# Sheet1.net
KiCad netlist of a schematic drawn in Altium Designer
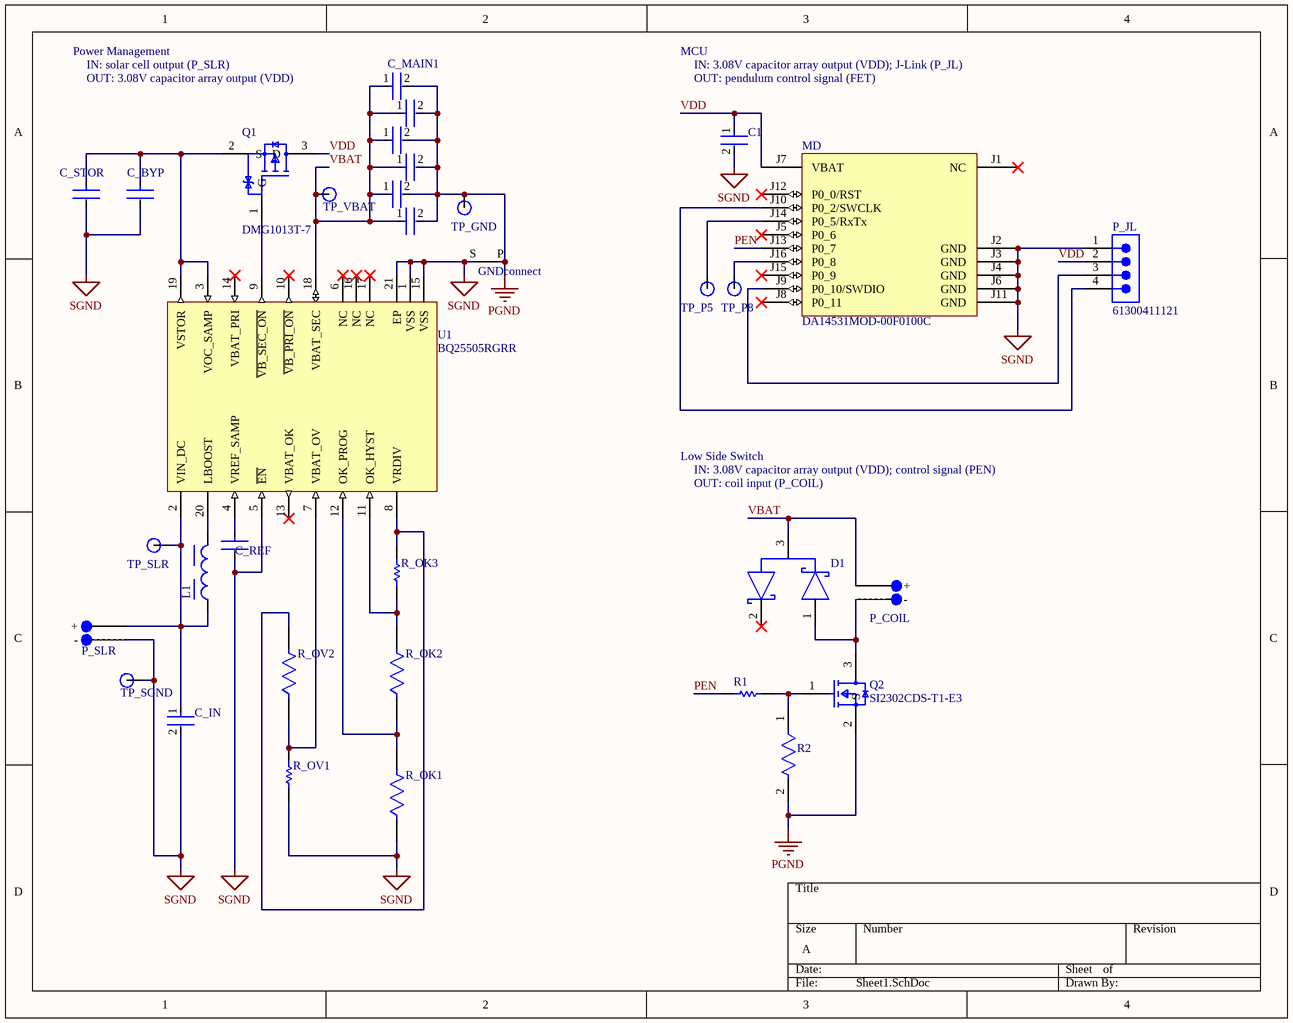
[diagram p0: Sheet1.SchDoc]

(export (version "E")
  (design (tool "Eeschema 10.0.6"))
  (components
    (comp (ref "C1")
      (value "GRM188R72A104KA35D")
      (footprint "FP-GRM188-0_1-e0_2_0_5-IPC_B")
      (description "Chip Multilayer Ceramic Capacitors for General Purpose, 0603, 0.10uF, X7R, 15%, 10%, 100V")
      (fields (field (name "VOLTAGE") "100V") (field (name "TOLERANCE") "10%"))
      (libsource (lib "Altium Content Vault") (part "11868f565c42a9108669ba33697ecf6"))
    )
    (comp (ref "C_BYP")
      (value "CGA4J1X7R1H475K125AC")
      (footprint "FP-CGA4J-IPC_C")
      (description "Cap Ceramic 4.7uF 50V X7R 10% Pad SMD 0805 +125°C Automotive T/R")
      (libsource (lib "") (part "b4654b650e69147ec39a6b967a45e02_1"))
    )
    (comp (ref "C_IN")
      (value "CGA4J1X7R1H475K125AC")
      (footprint "FP-CGA4J-IPC_C")
      (description "Cap Ceramic 4.7uF 50V X7R 10% Pad SMD 0805 +125°C Automotive T/R")
      (libsource (lib "Altium Content Vault") (part "b4654b650e69147ec39a6b967a45e02"))
    )
    (comp (ref "C_MAIN1")
      (value "GRM32ER60J227ME05L")
      (footprint "FP-GRM32E-0_3-MFG")
      (description "Chip Multilayer Ceramic Capacitors for General Purpose, 1210, 220uF, X5R, 15%, 20%, 6.3V")
      (fields (field (name "TOLERANCE") "20%"))
      (libsource (lib "Altium Content Vault") (part "b4654b650e69147ec39a6b967a45e02"))
    )
    (comp (ref "C_MAIN2")
      (value "GRM32ER60J227ME05L")
      (footprint "FP-GRM32E-0_3-MFG")
      (description "Chip Multilayer Ceramic Capacitors for General Purpose, 1210, 220uF, X5R, 15%, 20%, 6.3V")
      (fields (field (name "TOLERANCE") "20%"))
      (libsource (lib "Altium Content Vault") (part "b4654b650e69147ec39a6b967a45e02"))
    )
    (comp (ref "C_MAIN3")
      (value "GRM32ER60J227ME05L")
      (footprint "FP-GRM32E-0_3-MFG")
      (description "Chip Multilayer Ceramic Capacitors for General Purpose, 1210, 220uF, X5R, 15%, 20%, 6.3V")
      (fields (field (name "TOLERANCE") "20%"))
      (libsource (lib "Altium Content Vault") (part "b4654b650e69147ec39a6b967a45e02"))
    )
    (comp (ref "C_MAIN4")
      (value "GRM32ER60J227ME05L")
      (footprint "FP-GRM32E-0_3-MFG")
      (description "Chip Multilayer Ceramic Capacitors for General Purpose, 1210, 220uF, X5R, 15%, 20%, 6.3V")
      (fields (field (name "TOLERANCE") "20%"))
      (libsource (lib "Altium Content Vault") (part "b4654b650e69147ec39a6b967a45e02"))
    )
    (comp (ref "C_MAIN5")
      (value "GRM32ER60J227ME05L")
      (footprint "FP-GRM32E-0_3-MFG")
      (description "Chip Multilayer Ceramic Capacitors for General Purpose, 1210, 220uF, X5R, 15%, 20%, 6.3V")
      (fields (field (name "TOLERANCE") "20%"))
      (libsource (lib "Altium Content Vault") (part "b4654b650e69147ec39a6b967a45e02"))
    )
    (comp (ref "C_MAIN6")
      (value "GRM32ER60J227ME05L")
      (footprint "FP-GRM32E-0_3-MFG")
      (description "Chip Multilayer Ceramic Capacitors for General Purpose, 1210, 220uF, X5R, 15%, 20%, 6.3V")
      (fields (field (name "TOLERANCE") "20%"))
      (libsource (lib "Altium Content Vault") (part "b4654b650e69147ec39a6b967a45e02"))
    )
    (comp (ref "C_REF")
      (value "GCM188R72A103KA37D")
      (footprint "FP-GCM188-0_1-MFG")
      (description "Ceramic Capacitor for Automotive 10nF  ±10% 100VDC X7R 0603 Paper T/R")
      (fields (field (name "VOLTAGE") "100V") (field (name "TOLERANCE") "10%"))
      (libsource (lib "Altium Content Vault") (part "02cd4be3c70576c341d710602a673aa"))
    )
    (comp (ref "C_STOR")
      (value "GCM188R72A103KA37D")
      (footprint "FP-GCM188-0_1-MFG")
      (description "Ceramic Capacitor for Automotive 10nF  ±10% 100VDC X7R 0603 Paper T/R")
      (fields (field (name "VOLTAGE") "100V") (field (name "TOLERANCE") "10%"))
      (libsource (lib "Altium Content Vault") (part "02cd4be3c70576c341d710602a673aa"))
    )
    (comp (ref "D1")
      (value "BAT54STA")
      (footprint "FP-SOT523-MFG")
      (description "DIODE ARRAY SCHOTTKY 30V SOT23-3")
      (fields
        (field (name "OCTOPART") "https://octopart.com/bat54sta-diodes+inc.-326178")
        (field (name "MANUFACTURER") "Diodes Inc.")
      )
      (libsource (lib "Altium Content Vault") (part "3154784a5abab095c2c910d688c1447"))
    )
    (comp (ref "GNDconnect")
      (value "GNDconnect")
      (footprint "GNDconnect")
      (libsource (lib "Schlib1") (part "GNDconnect"))
    )
    (comp (ref "L1")
      (value "744031220")
      (footprint "WE-TPC_3816")
      (description "Tiny Power Inductor, SMT, Fixed, 22UH, .51A, .041 Ohm, 3816, We-tpc Series")
      (fields (field (name "TOLERANCE") "30%"))
      (libsource (lib "Altium Content Vault") (part "Inductor - 3"))
    )
    (comp (ref "MD")
      (value "DA14531MOD-00F0100C")
      (footprint "MN0016AA_MFG")
      (description "SmartBond TINY Bluetooth Low Energy Module")
      (libsource (lib "Altium Content Vault") (part "3c23fbc519b76c76d1d6908b3b5f111"))
    )
    (comp (ref "P_COIL")
      (value "Paired_pads")
      (footprint "Paired_pads")
      (libsource (lib "") (part "Paired_pads_1"))
    )
    (comp (ref "P_JL")
      (value "61300411121")
      (footprint "61300411121")
      (description "THT Vertical Pin Header WR-PHD, Pitch 2.54 mm, Single Row, 4 pins")
      (libsource (lib "Altium Content Vault") (part "Header_Male_1R_04P"))
    )
    (comp (ref "P_SLR")
      (value "Paired_pads")
      (footprint "Paired_pads")
      (libsource (lib "Schlib2") (part "Paired_pads"))
    )
    (comp (ref "Q1")
      (value "DMG1013T-7")
      (footprint "FP-SOT523-IPC_B")
      (description "MOSFET P-CH 20V 0.46A SOT-523")
      (libsource (lib "Altium Content Vault") (part "d2c0d31e441d0c4ace7f3b05f74b3be"))
    )
    (comp (ref "Q2")
      (value "SI2302CDS-T1-E3")
      (footprint "FP-S-03946-MFG")
      (description "MOSFET N-CH 20V 2.6A SOT-23")
      (fields
        (field (name "MANUFACTURER") "Vishay")
        (field (name "OCTOPART") "https://octopart.com/si2302cds-t1-e3-vishay-44452855")
      )
      (libsource (lib "Altium Content Vault") (part "3b9c635fedb024a5347a57b145af9cc"))
    )
    (comp (ref "R1")
      (value "ERJ-3EKF4700V")
      (footprint "RESC1608X55X30ML15T15")
      (description "Chip Resistor, 470 Ohm, +/- 1%, 0.1 W, -55 to 155 degC, 0603 (1608 Metric), RoHS, Tape and Reel")
      (fields (field (name "MANUFACTURER") "Panasonic"))
      (libsource (lib "Altium Content Vault") (part "RES-2"))
    )
    (comp (ref "R2")
      (value "RC0603FR-07100KL")
      (footprint "FP-RC0603-0_55-MFG")
      (description "RES SMD 100K OHM 1% 1/10W 0603")
      (fields (field (name "TOLERANCE") "1%"))
      (libsource (lib "") (part "1029c3af85768c4190bb7ad29bc67b5_1"))
    )
    (comp (ref "R_OK1")
      (value "CRCW06035M62FKEA")
      (footprint "FP-CRCW0603-e3-IPC_B")
      (description "RES Thick Film, 5.62MΩ, 1%, 0.1W, 100ppm/°C, 0603")
      (fields (field (name "TOLERANCE") "1%"))
      (libsource (lib "Altium Content Vault") (part "1029c3af85768c4190bb7ad29bc67b5"))
    )
    (comp (ref "R_OK2")
      (value "CRCW06035M49FKEA")
      (footprint "FP-CRCW0603-e3-IPC_C")
      (description "RES Thick Film, 5.49MΩ, 1%, 0.1W, 100ppm/°C, 0603")
      (fields (field (name "TOLERANCE") "1%"))
      (libsource (lib "Altium Content Vault") (part "1029c3af85768c4190bb7ad29bc67b5"))
    )
    (comp (ref "R_OK3")
      (value "CRCW06031M87FKEA")
      (footprint "RESC1609X50X30ML10T20")
      (fields (field (name "MANUFACTURER") "Vishay Dale"))
      (libsource (lib "Altium Content Vault") (part "RES"))
    )
    (comp (ref "R_OV1")
      (value "CRCW06037M68FKEA")
      (footprint "RESC0603(1608)_L")
      (description "7M68 0.1W 1% 0603 (1608 Metric)  SMD")
      (fields (field (name "POWER") "0.1 W") (field (name "TOLERANCE") "1 %"))
      (libsource (lib "Altium Content Vault") (part "RES"))
    )
    (comp (ref "R_OV2")
      (value "CRCW06035M36FKEA")
      (footprint "FP-CRCW0603-e3-IPC_C")
      (description "RES Thick Film, 5.36MΩ, 1%, 0.1W, 100ppm/°C, 0603")
      (fields (field (name "TOLERANCE") "1%"))
      (libsource (lib "Altium Content Vault") (part "1029c3af85768c4190bb7ad29bc67b5"))
    )
    (comp (ref "TP_GND") (value "TP") (footprint "Test_point") (libsource (lib "Schlib3") (part "TP")))
    (comp (ref "TP_P5") (value "TP") (footprint "Test_point") (libsource (lib "Schlib3") (part "TP")))
    (comp (ref "TP_P8") (value "TP") (footprint "Test_point") (libsource (lib "Schlib3") (part "TP")))
    (comp (ref "TP_SGND") (value "TP") (footprint "Test_point") (libsource (lib "Schlib3") (part "TP")))
    (comp (ref "TP_SLR") (value "TP") (footprint "Test_point") (libsource (lib "Schlib3") (part "TP")))
    (comp (ref "TP_VBAT") (value "TP") (footprint "Test_point") (libsource (lib "Schlib3") (part "TP")))
    (comp (ref "U1")
      (value "BQ25505RGRR")
      (footprint "RGR0020A_V")
      (fields (field (name "GENERIC PART NUMBER") "BQ25505"))
      (libsource (lib "Altium Content Vault") (part "TI-BQ25505-RGR-20"))
    )
  )
  (nets
    (net (code "1") (name "/PEN") (class "Default")
      (node (ref "MD") (pin "J13") (pinfunction "P0_7_J13") (pintype "bidirectional"))
      (node (ref "R1") (pin "1") (pinfunction "1_1") (pintype "passive"))
    )
    (net (code "2") (name "/VBAT") (class "Default")
      (node (ref "C_MAIN1") (pin "1") (pinfunction "1_1") (pintype "passive"))
      (node (ref "C_MAIN2") (pin "1") (pinfunction "1_1") (pintype "passive"))
      (node (ref "C_MAIN3") (pin "1") (pinfunction "1_1") (pintype "passive"))
      (node (ref "C_MAIN4") (pin "1") (pinfunction "1_1") (pintype "passive"))
      (node (ref "C_MAIN5") (pin "1") (pinfunction "1_1") (pintype "passive"))
      (node (ref "C_MAIN6") (pin "1") (pinfunction "1_1") (pintype "passive"))
      (node (ref "D1") (pin "3") (pinfunction "3_3") (pintype "passive"))
      (node (ref "P_COIL") (pin "1") (pinfunction "+_1") (pintype "passive"))
      (node (ref "TP_VBAT") (pin "1") (pinfunction "TP_1") (pintype "passive"))
      (node (ref "U1") (pin "18") (pinfunction "VBAT_SEC_18") (pintype "bidirectional"))
    )
    (net (code "3") (name "/VDD") (class "Default")
      (node (ref "C1") (pin "1") (pinfunction "1_1") (pintype "passive"))
      (node (ref "MD") (pin "J7") (pinfunction "VBAT_J7") (pintype "power_in"))
      (node (ref "P_JL") (pin "2") (pinfunction "2_2") (pintype "passive"))
      (node (ref "Q1") (pin "3") (pinfunction "D_3") (pintype "passive"))
    )
    (net (code "4") (name "Net-(MD-P0_2{slash}SWCLK)") (class "Default")
      (node (ref "MD") (pin "J10") (pinfunction "P0_2/SWCLK_J10") (pintype "bidirectional"))
      (node (ref "P_JL") (pin "4") (pinfunction "4_4") (pintype "passive"))
    )
    (net (code "5") (name "Net-(MD-P0_5{slash}RxTx)") (class "Default")
      (node (ref "MD") (pin "J14") (pinfunction "P0_5/RxTx_J14") (pintype "bidirectional"))
      (node (ref "TP_P5") (pin "1") (pinfunction "TP_1") (pintype "passive"))
    )
    (net (code "6") (name "Net-(MD-P0_8)") (class "Default")
      (node (ref "MD") (pin "J16") (pinfunction "P0_8_J16") (pintype "bidirectional"))
      (node (ref "TP_P8") (pin "1") (pinfunction "TP_1") (pintype "passive"))
    )
    (net (code "7") (name "Net-(MD-P0_10{slash}SWDIO)") (class "Default")
      (node (ref "MD") (pin "J9") (pinfunction "P0_10/SWDIO_J9") (pintype "bidirectional"))
      (node (ref "P_JL") (pin "3") (pinfunction "3_3") (pintype "passive"))
    )
    (net (code "8") (name "Net-(P_COIL--)") (class "Default")
      (node (ref "D1") (pin "1") (pinfunction "1_1") (pintype "passive"))
      (node (ref "P_COIL") (pin "2") (pinfunction "-_2") (pintype "passive"))
      (node (ref "Q2") (pin "3") (pinfunction "D_3") (pintype "passive"))
    )
    (net (code "9") (name "Net-(P_SLR-+)") (class "Default")
      (node (ref "C_IN") (pin "1") (pinfunction "1_1") (pintype "passive"))
      (node (ref "L1") (pin "1") (pinfunction "1_1") (pintype "passive"))
      (node (ref "P_SLR") (pin "1") (pinfunction "+_1") (pintype "passive"))
      (node (ref "TP_SLR") (pin "1") (pinfunction "TP_1") (pintype "passive"))
      (node (ref "U1") (pin "2") (pinfunction "VIN_DC_2") (pintype "power_in"))
    )
    (net (code "10") (name "Net-(Q1-G)") (class "Default")
      (node (ref "Q1") (pin "1") (pinfunction "G_1") (pintype "passive"))
      (node (ref "U1") (pin "9") (pinfunction "~{VB_SEC_ON}_9") (pintype "output"))
    )
    (net (code "11") (name "Net-(Q1-S)") (class "Default")
      (node (ref "C_BYP") (pin "1") (pinfunction "1_1") (pintype "passive"))
      (node (ref "C_STOR") (pin "1") (pinfunction "1_1") (pintype "passive"))
      (node (ref "Q1") (pin "2") (pinfunction "S_2") (pintype "passive"))
      (node (ref "U1") (pin "19") (pinfunction "VSTOR_19") (pintype "output"))
      (node (ref "U1") (pin "3") (pinfunction "VOC_SAMP_3") (pintype "input"))
    )
    (net (code "12") (name "Net-(Q2-G)") (class "Default")
      (node (ref "Q2") (pin "1") (pinfunction "G_1") (pintype "passive"))
      (node (ref "R1") (pin "2") (pinfunction "2_2") (pintype "passive"))
      (node (ref "R2") (pin "1") (pinfunction "1_1") (pintype "passive"))
    )
    (net (code "13") (name "Net-(U1-LBOOST)") (class "Default")
      (node (ref "L1") (pin "2") (pinfunction "2_2") (pintype "passive"))
      (node (ref "U1") (pin "20") (pinfunction "LBOOST_20") (pintype "power_in"))
    )
    (net (code "14") (name "Net-(U1-OK_HYST)") (class "Default")
      (node (ref "R_OK2") (pin "2") (pinfunction "2_2") (pintype "passive"))
      (node (ref "R_OK3") (pin "1") (pinfunction "1_1") (pintype "passive"))
      (node (ref "U1") (pin "11") (pinfunction "OK_HYST_11") (pintype "input"))
    )
    (net (code "15") (name "Net-(U1-OK_PROG)") (class "Default")
      (node (ref "R_OK1") (pin "2") (pinfunction "2_2") (pintype "passive"))
      (node (ref "R_OK2") (pin "1") (pinfunction "1_1") (pintype "passive"))
      (node (ref "U1") (pin "12") (pinfunction "OK_PROG_12") (pintype "input"))
    )
    (net (code "16") (name "Net-(U1-VBAT_OV)") (class "Default")
      (node (ref "R_OV1") (pin "2") (pinfunction "2_2") (pintype "passive"))
      (node (ref "R_OV2") (pin "1") (pinfunction "1_1") (pintype "passive"))
      (node (ref "U1") (pin "7") (pinfunction "VBAT_OV_7") (pintype "input"))
    )
    (net (code "17") (name "Net-(U1-VRDIV)") (class "Default")
      (node (ref "R_OK3") (pin "2") (pinfunction "2_2") (pintype "passive"))
      (node (ref "R_OV2") (pin "2") (pinfunction "2_2") (pintype "passive"))
      (node (ref "U1") (pin "8") (pinfunction "VRDIV_8") (pintype "power_in"))
    )
    (net (code "18") (name "Net-(U1-VREF_SAMP)") (class "Default")
      (node (ref "C_REF") (pin "1") (pinfunction "1_1") (pintype "passive"))
      (node (ref "U1") (pin "4") (pinfunction "VREF_SAMP_4") (pintype "input"))
    )
    (net (code "19") (name "PGND") (class "Default")
      (node (ref "C_MAIN1") (pin "2") (pinfunction "2_2") (pintype "passive"))
      (node (ref "C_MAIN2") (pin "2") (pinfunction "2_2") (pintype "passive"))
      (node (ref "C_MAIN3") (pin "2") (pinfunction "2_2") (pintype "passive"))
      (node (ref "C_MAIN4") (pin "2") (pinfunction "2_2") (pintype "passive"))
      (node (ref "C_MAIN5") (pin "2") (pinfunction "2_2") (pintype "passive"))
      (node (ref "C_MAIN6") (pin "2") (pinfunction "2_2") (pintype "passive"))
      (node (ref "GNDconnect") (pin "P") (pinfunction "P_P") (pintype "passive"))
      (node (ref "Q2") (pin "2") (pinfunction "S_2") (pintype "passive"))
      (node (ref "R2") (pin "2") (pinfunction "2_2") (pintype "passive"))
      (node (ref "TP_GND") (pin "1") (pinfunction "TP_1") (pintype "passive"))
    )
    (net (code "20") (name "SGND") (class "Default")
      (node (ref "C1") (pin "2") (pinfunction "2_2") (pintype "passive"))
      (node (ref "C_BYP") (pin "2") (pinfunction "2_2") (pintype "passive"))
      (node (ref "C_IN") (pin "2") (pinfunction "2_2") (pintype "passive"))
      (node (ref "C_REF") (pin "2") (pinfunction "2_2") (pintype "passive"))
      (node (ref "C_STOR") (pin "2") (pinfunction "2_2") (pintype "passive"))
      (node (ref "GNDconnect") (pin "S") (pinfunction "S_S") (pintype "passive"))
      (node (ref "MD") (pin "J11") (pinfunction "GND_J11") (pintype "power_in"))
      (node (ref "MD") (pin "J2") (pinfunction "GND_J2") (pintype "power_in"))
      (node (ref "MD") (pin "J3") (pinfunction "GND_J3") (pintype "power_in"))
      (node (ref "MD") (pin "J4") (pinfunction "GND_J4") (pintype "power_in"))
      (node (ref "MD") (pin "J6") (pinfunction "GND_J6") (pintype "power_in"))
      (node (ref "P_JL") (pin "1") (pinfunction "1_1") (pintype "passive"))
      (node (ref "P_SLR") (pin "2") (pinfunction "-_2") (pintype "passive"))
      (node (ref "R_OK1") (pin "1") (pinfunction "1_1") (pintype "passive"))
      (node (ref "R_OV1") (pin "1") (pinfunction "1_1") (pintype "passive"))
      (node (ref "TP_SGND") (pin "1") (pinfunction "TP_1") (pintype "passive"))
      (node (ref "U1") (pin "1") (pinfunction "VSS_1") (pintype "power_in"))
      (node (ref "U1") (pin "15") (pinfunction "VSS_15") (pintype "power_in"))
      (node (ref "U1") (pin "21") (pinfunction "EP_21") (pintype "passive"))
      (node (ref "U1") (pin "5") (pinfunction "~{EN}_5") (pintype "input"))
    )
    (net (code "21") (name "unconnected-(D1-Pad2)") (class "Default")
      (node (ref "D1") (pin "2") (pinfunction "2_2") (pintype "passive+no_connect"))
    )
    (net (code "22") (name "unconnected-(MD-NC-PadJ1)") (class "Default")
      (node (ref "MD") (pin "J1") (pinfunction "NC_J1") (pintype "passive+no_connect"))
    )
    (net (code "23") (name "unconnected-(MD-P0_0{slash}RST-PadJ12)") (class "Default")
      (node (ref "MD") (pin "J12") (pinfunction "P0_0/RST_J12") (pintype "bidirectional+no_connect"))
    )
    (net (code "24") (name "unconnected-(MD-P0_6-PadJ5)") (class "Default")
      (node (ref "MD") (pin "J5") (pinfunction "P0_6_J5") (pintype "bidirectional+no_connect"))
    )
    (net (code "25") (name "unconnected-(MD-P0_9-PadJ15)") (class "Default")
      (node (ref "MD") (pin "J15") (pinfunction "P0_9_J15") (pintype "bidirectional+no_connect"))
    )
    (net (code "26") (name "unconnected-(MD-P0_11-PadJ8)") (class "Default")
      (node (ref "MD") (pin "J8") (pinfunction "P0_11_J8") (pintype "bidirectional+no_connect"))
    )
    (net (code "27") (name "unconnected-(U1-NC-Pad6)") (class "Default")
      (node (ref "U1") (pin "6") (pinfunction "NC_6") (pintype "passive+no_connect"))
    )
    (net (code "28") (name "unconnected-(U1-NC-Pad16)") (class "Default")
      (node (ref "U1") (pin "16") (pinfunction "NC_16") (pintype "passive+no_connect"))
    )
    (net (code "29") (name "unconnected-(U1-NC-Pad17)") (class "Default")
      (node (ref "U1") (pin "17") (pinfunction "NC_17") (pintype "passive+no_connect"))
    )
    (net (code "30") (name "unconnected-(U1-VBAT_OK-Pad13)") (class "Default")
      (node (ref "U1") (pin "13") (pinfunction "VBAT_OK_13") (pintype "output+no_connect"))
    )
    (net (code "31") (name "unconnected-(U1-VBAT_PRI-Pad14)") (class "Default")
      (node (ref "U1") (pin "14") (pinfunction "VBAT_PRI_14") (pintype "input+no_connect"))
    )
    (net (code "32") (name "unconnected-(U1-~{VB_PRI_ON}-Pad10)") (class "Default")
      (node (ref "U1") (pin "10") (pinfunction "~{VB_PRI_ON}_10") (pintype "output+no_connect"))
    )
  )
)
